# moire_v1_2_rtb.net
KiCad netlist of a schematic drawn in EAGLE
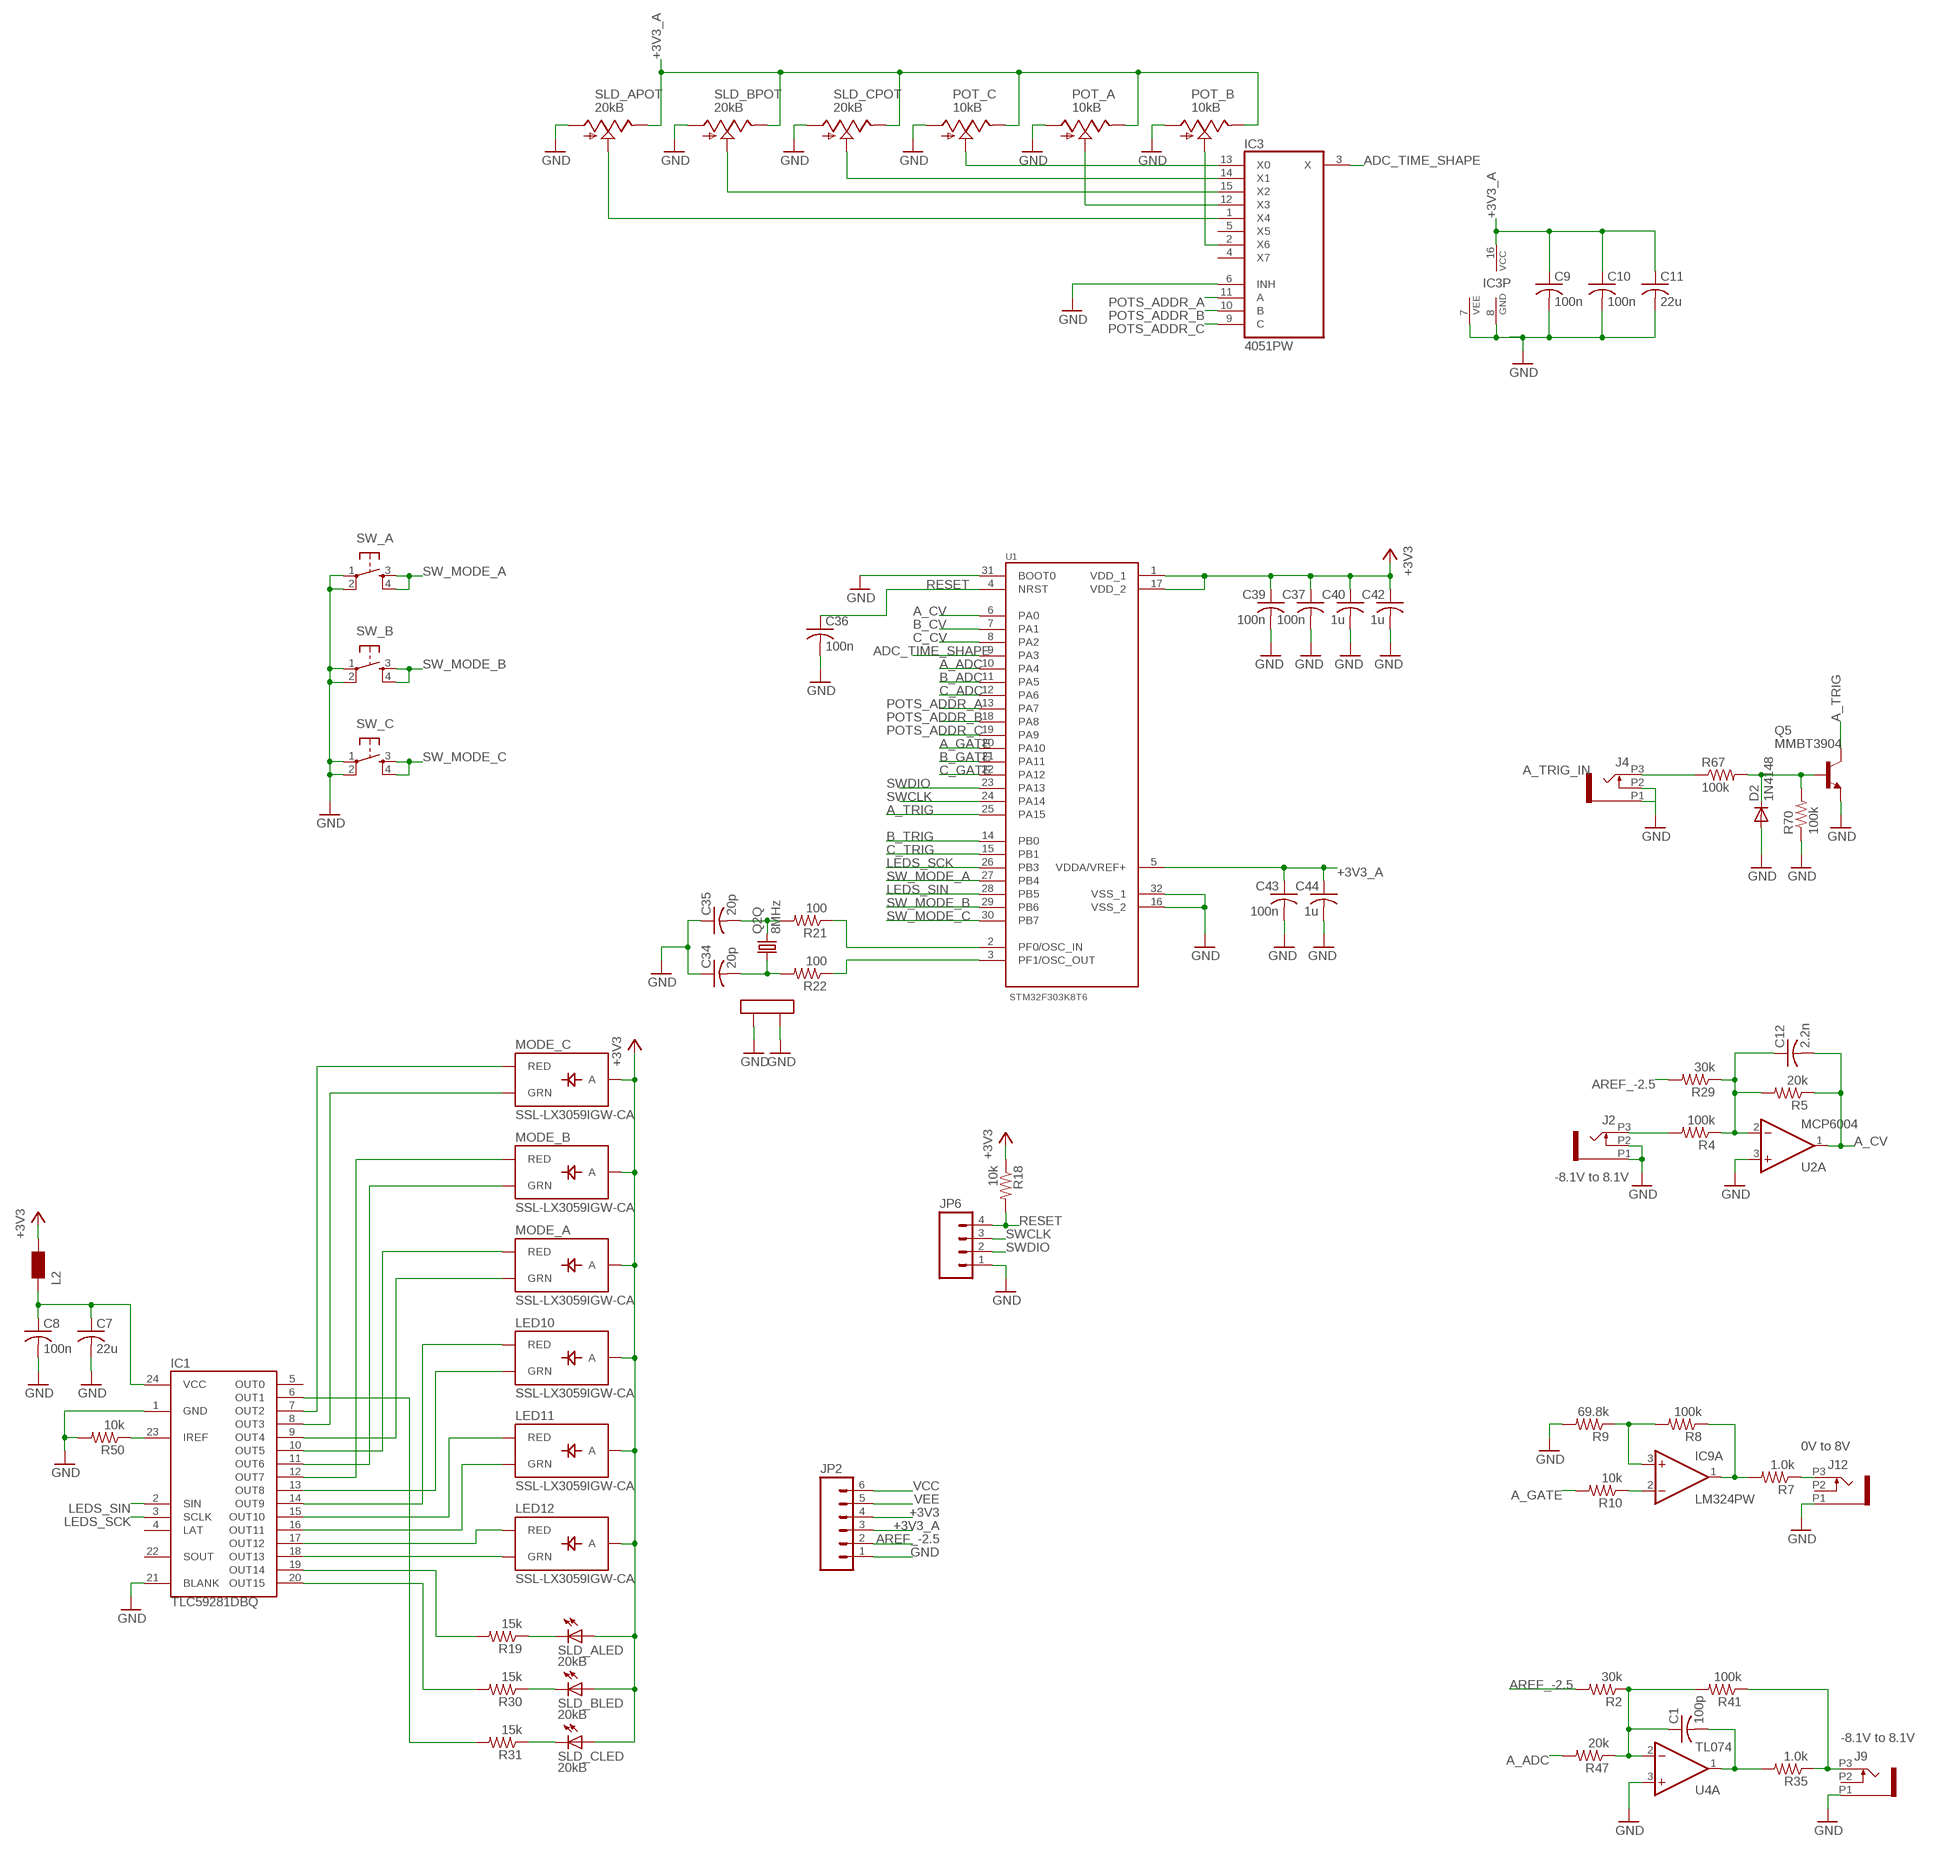
[diagram p0: schematic, sheet 1, part 1 of 2]
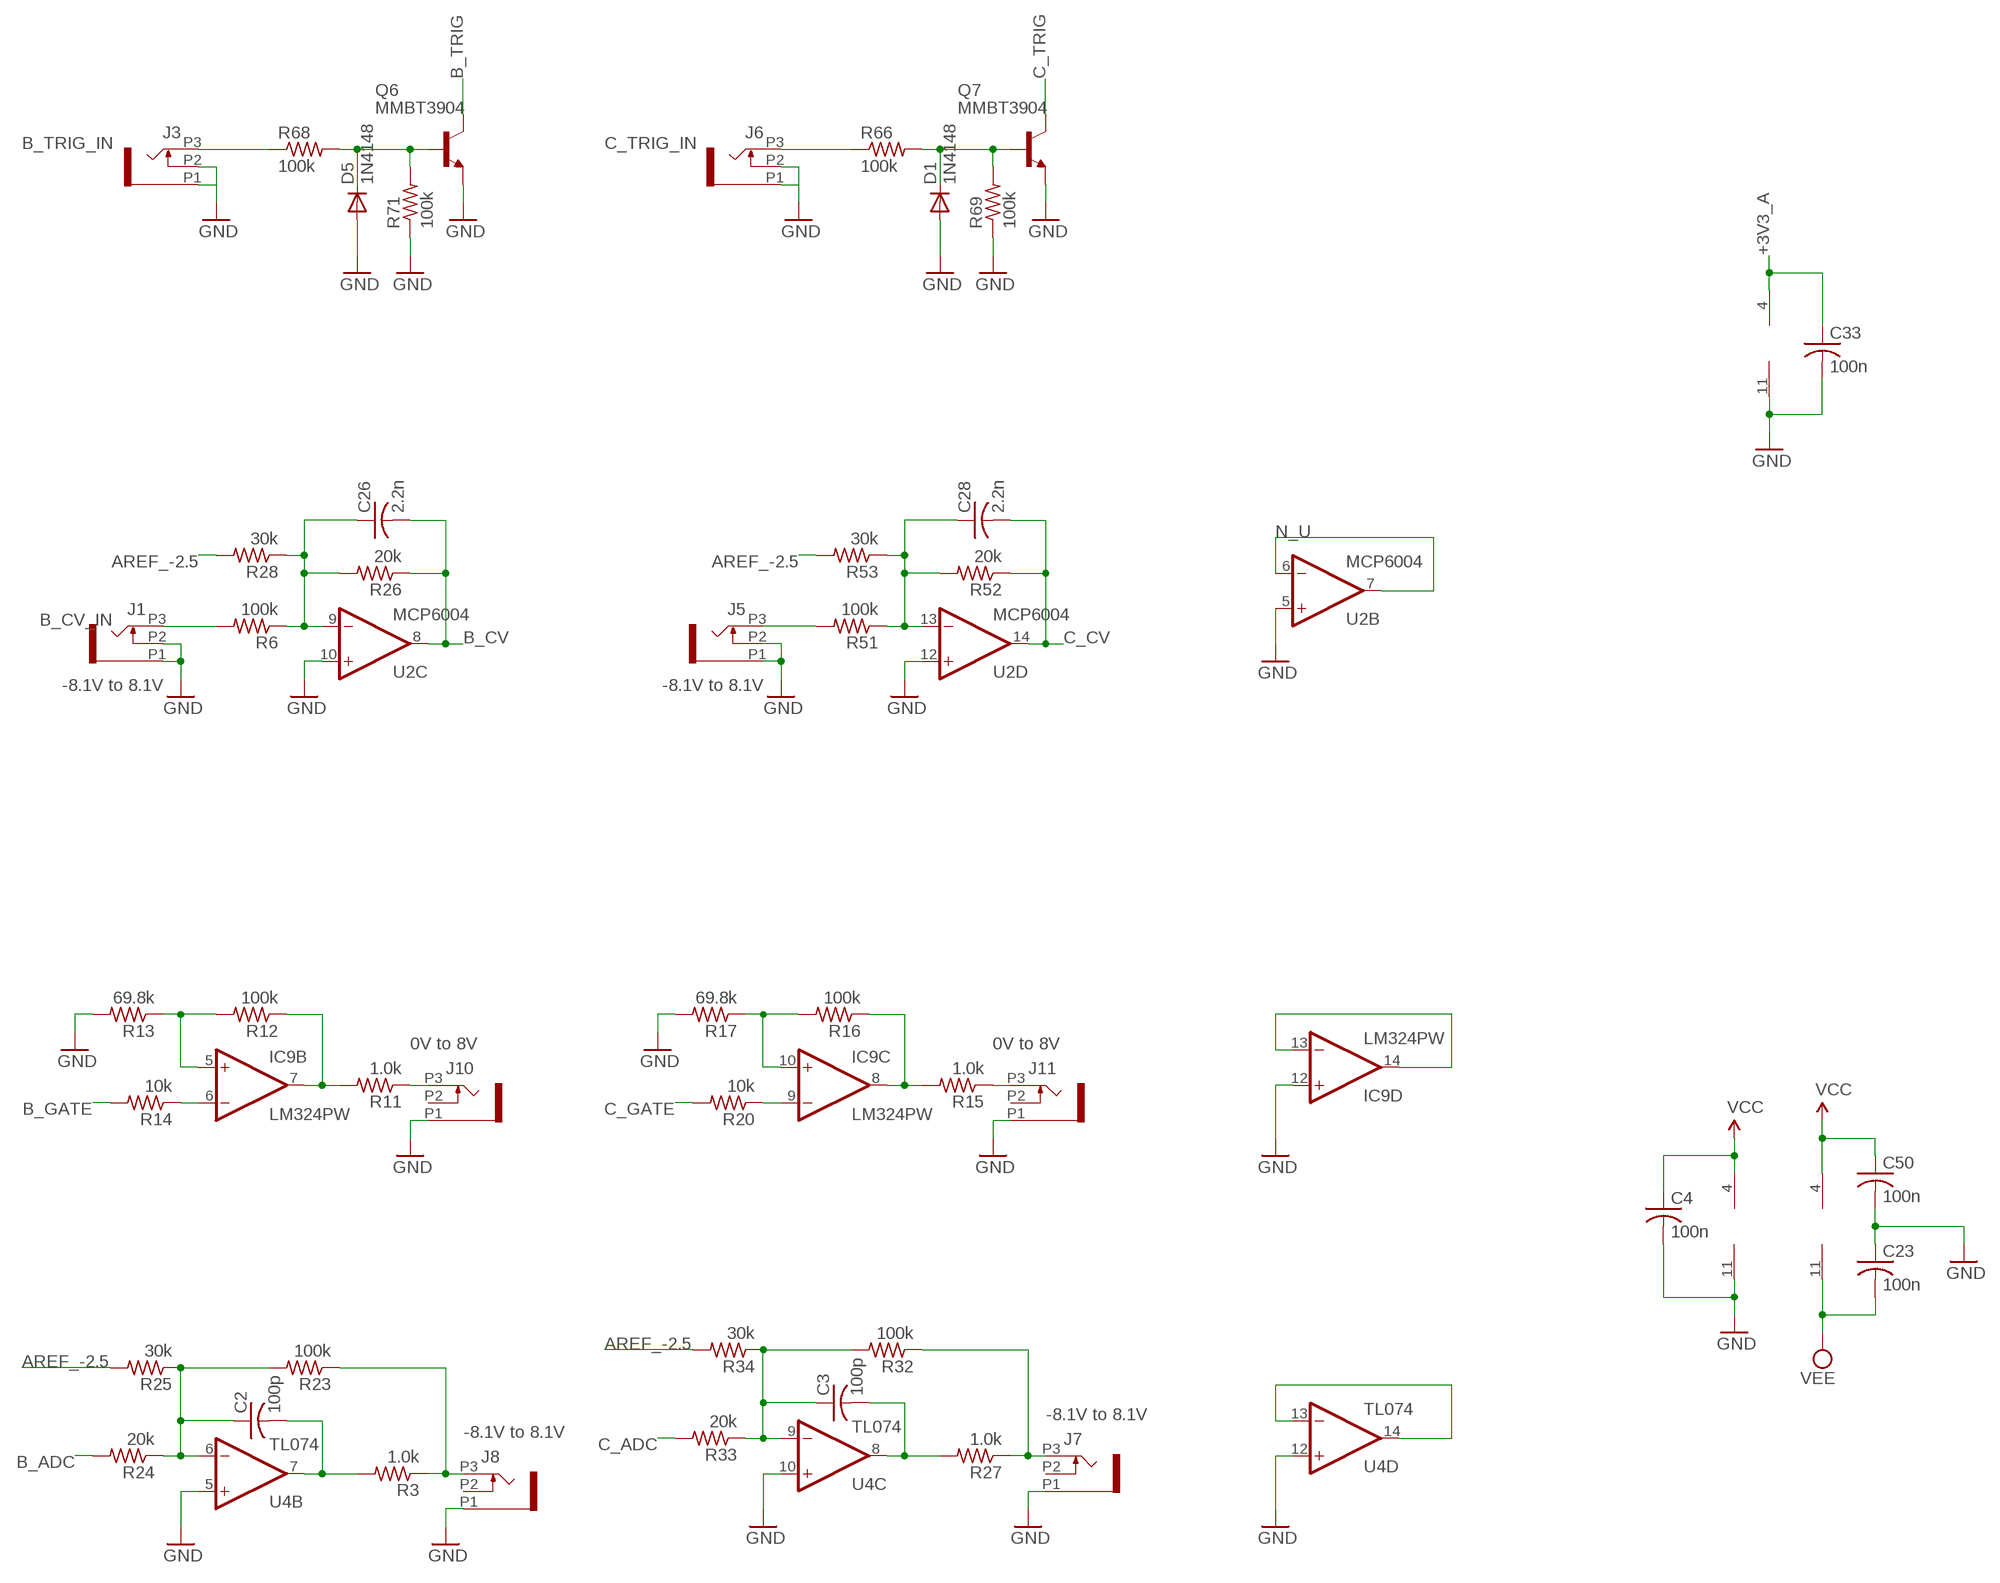
[diagram p1: schematic, sheet 1, part 2 of 2]
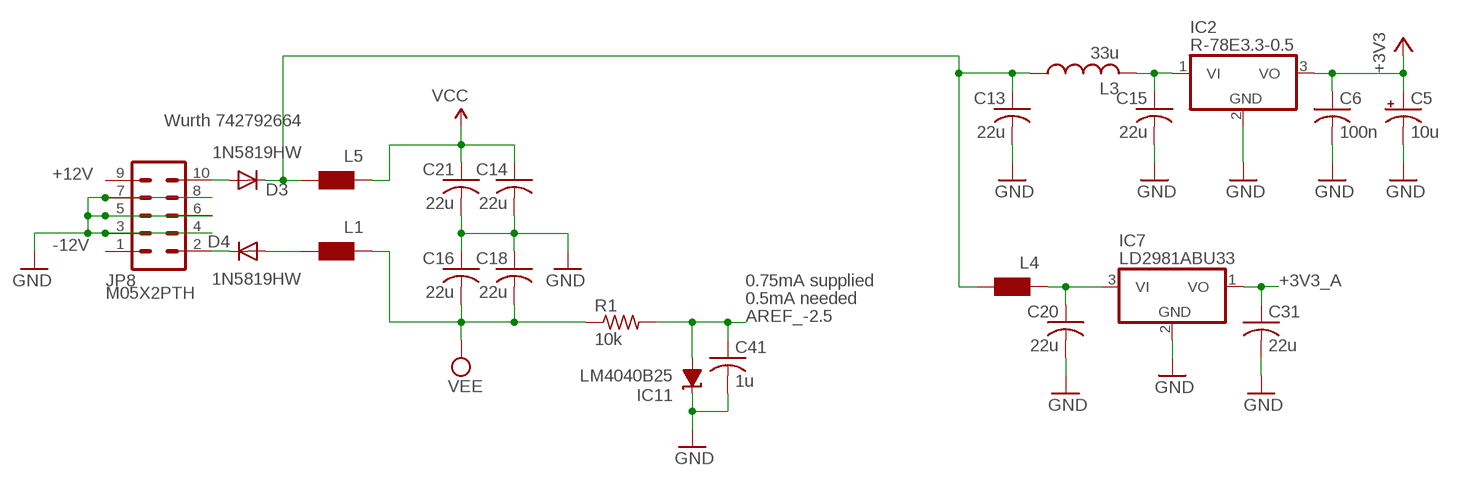
[diagram p2: schematic, sheet 2]

(export (version "E")
  (design (tool "Eeschema 10.0.6"))
  (components
    (comp (ref "C5")
      (value "10u")
      (footprint "eagle-import:PANASONIC_A")
      (libsource (lib "eagle-import") (part "CPOL-USA"))
    )
    (comp (ref "C6")
      (value "100n")
      (footprint "eagle-import:C0603")
      (libsource (lib "eagle-import") (part "C-USC0603"))
    )
    (comp (ref "C13")
      (value "22u")
      (footprint "eagle-import:C1206")
      (libsource (lib "eagle-import") (part "C-USC1206"))
    )
    (comp (ref "C14")
      (value "22u")
      (footprint "eagle-import:C1206")
      (libsource (lib "eagle-import") (part "C-USC1206"))
    )
    (comp (ref "C15")
      (value "22u")
      (footprint "eagle-import:C1206")
      (libsource (lib "eagle-import") (part "C-USC1206"))
    )
    (comp (ref "C16")
      (value "22u")
      (footprint "eagle-import:C1206")
      (libsource (lib "eagle-import") (part "C-USC1206"))
    )
    (comp (ref "C18")
      (value "22u")
      (footprint "eagle-import:C1206")
      (libsource (lib "eagle-import") (part "C-USC1206"))
    )
    (comp (ref "C20")
      (value "22u")
      (footprint "eagle-import:C1206")
      (libsource (lib "eagle-import") (part "C-USC1206"))
    )
    (comp (ref "C21")
      (value "22u")
      (footprint "eagle-import:C1206")
      (libsource (lib "eagle-import") (part "C-USC1206"))
    )
    (comp (ref "C31")
      (value "22u")
      (footprint "eagle-import:C1206")
      (libsource (lib "eagle-import") (part "C-USC1206"))
    )
    (comp (ref "C41")
      (value "1u")
      (footprint "eagle-import:C0603")
      (libsource (lib "eagle-import") (part "C-USC0603"))
    )
    (comp (ref "D3")
      (value "1N5819HW")
      (footprint "eagle-import:SOD123")
      (libsource (lib "eagle-import") (part "DIODE-SOD123"))
    )
    (comp (ref "D4")
      (value "1N5819HW")
      (footprint "eagle-import:SOD123")
      (libsource (lib "eagle-import") (part "DIODE-SOD123"))
    )
    (comp (ref "IC2")
      (value "R-78E3.3-0.5")
      (footprint "eagle-import:WE78")
      (libsource (lib "eagle-import") (part "WE173950378"))
    )
    (comp (ref "IC7")
      (value "LD2981ABU33")
      (footprint "eagle-import:SOT89")
      (libsource (lib "eagle-import") (part "LD2981ABU"))
    )
    (comp (ref "IC11")
      (value "LM4040B25")
      (footprint "eagle-import:DBZ_R-PDSO-G3")
      (libsource (lib "eagle-import") (part "LM4041DBZB12"))
    )
    (comp (ref "JP8")
      (value "M05X2PTH")
      (footprint "eagle-import:2X5-PTH")
      (libsource (lib "eagle-import") (part "M05X2PTH"))
    )
    (comp (ref "L1")
      (value "WE-CBF_0603")
      (footprint "eagle-import:0603")
      (libsource (lib "eagle-import") (part "WE-CBF_0603"))
    )
    (comp (ref "L3")
      (value "33u")
      (footprint "eagle-import:L2012C")
      (libsource (lib "eagle-import") (part "L-USL2012C"))
    )
    (comp (ref "L4")
      (value "WE-CBF_0603")
      (footprint "eagle-import:0603")
      (libsource (lib "eagle-import") (part "WE-CBF_0603"))
    )
    (comp (ref "L5")
      (value "WE-CBF_0603")
      (footprint "eagle-import:0603")
      (libsource (lib "eagle-import") (part "WE-CBF_0603"))
    )
    (comp (ref "R1")
      (value "10k")
      (footprint "eagle-import:R0603")
      (libsource (lib "eagle-import") (part "R-US_R0603"))
    )
    (comp (ref "C1")
      (value "100p")
      (footprint "eagle-import:C0603")
      (libsource (lib "eagle-import") (part "C-USC0603"))
    )
    (comp (ref "C2")
      (value "100p")
      (footprint "eagle-import:C0603")
      (libsource (lib "eagle-import") (part "C-USC0603"))
    )
    (comp (ref "C3")
      (value "100p")
      (footprint "eagle-import:C0603")
      (libsource (lib "eagle-import") (part "C-USC0603"))
    )
    (comp (ref "C4")
      (value "100n")
      (footprint "eagle-import:C0603")
      (libsource (lib "eagle-import") (part "C-USC0603"))
    )
    (comp (ref "C7")
      (value "22u")
      (footprint "eagle-import:C1206")
      (libsource (lib "eagle-import") (part "C-USC1206"))
    )
    (comp (ref "C8")
      (value "100n")
      (footprint "eagle-import:C0603")
      (libsource (lib "eagle-import") (part "C-USC0603"))
    )
    (comp (ref "C9")
      (value "100n")
      (footprint "eagle-import:C0603")
      (libsource (lib "eagle-import") (part "C-USC0603"))
    )
    (comp (ref "C10")
      (value "100n")
      (footprint "eagle-import:C0603")
      (libsource (lib "eagle-import") (part "C-USC0603"))
    )
    (comp (ref "C11")
      (value "22u")
      (footprint "eagle-import:C1206")
      (libsource (lib "eagle-import") (part "C-USC1206"))
    )
    (comp (ref "C12")
      (value "2.2n")
      (footprint "eagle-import:C0603")
      (libsource (lib "eagle-import") (part "C-USC0603"))
    )
    (comp (ref "C23")
      (value "100n")
      (footprint "eagle-import:C0603")
      (libsource (lib "eagle-import") (part "C-USC0603"))
    )
    (comp (ref "C26")
      (value "2.2n")
      (footprint "eagle-import:C0603")
      (libsource (lib "eagle-import") (part "C-USC0603"))
    )
    (comp (ref "C28")
      (value "2.2n")
      (footprint "eagle-import:C0603")
      (libsource (lib "eagle-import") (part "C-USC0603"))
    )
    (comp (ref "C33")
      (value "100n")
      (footprint "eagle-import:C0603")
      (libsource (lib "eagle-import") (part "C-USC0603"))
    )
    (comp (ref "C34")
      (value "20p")
      (footprint "eagle-import:C0603")
      (libsource (lib "eagle-import") (part "C-USC0603"))
    )
    (comp (ref "C35")
      (value "20p")
      (footprint "eagle-import:C0603")
      (libsource (lib "eagle-import") (part "C-USC0603"))
    )
    (comp (ref "C36")
      (value "100n")
      (footprint "eagle-import:C0603")
      (libsource (lib "eagle-import") (part "C-USC0603"))
    )
    (comp (ref "C37")
      (value "100n")
      (footprint "eagle-import:C0603")
      (libsource (lib "eagle-import") (part "C-USC0603"))
    )
    (comp (ref "C39")
      (value "100n")
      (footprint "eagle-import:C0603")
      (libsource (lib "eagle-import") (part "C-USC0603"))
    )
    (comp (ref "C40")
      (value "1u")
      (footprint "eagle-import:C0603")
      (libsource (lib "eagle-import") (part "C-USC0603"))
    )
    (comp (ref "C42")
      (value "1u")
      (footprint "eagle-import:C0603")
      (libsource (lib "eagle-import") (part "C-USC0603"))
    )
    (comp (ref "C43")
      (value "100n")
      (footprint "eagle-import:C0603")
      (libsource (lib "eagle-import") (part "C-USC0603"))
    )
    (comp (ref "C44")
      (value "1u")
      (footprint "eagle-import:C0603")
      (libsource (lib "eagle-import") (part "C-USC0603"))
    )
    (comp (ref "C50")
      (value "100n")
      (footprint "eagle-import:C0603")
      (libsource (lib "eagle-import") (part "C-USC0603"))
    )
    (comp (ref "D1")
      (value "1N4148")
      (footprint "eagle-import:SOD523")
      (libsource (lib "eagle-import") (part "DIODE-SOD523"))
    )
    (comp (ref "D2")
      (value "1N4148")
      (footprint "eagle-import:SOD523")
      (libsource (lib "eagle-import") (part "DIODE-SOD523"))
    )
    (comp (ref "D5")
      (value "1N4148")
      (footprint "eagle-import:SOD523")
      (libsource (lib "eagle-import") (part "DIODE-SOD523"))
    )
    (comp (ref "IC1")
      (value "TLC59281DBQ")
      (footprint "eagle-import:TSSOP24_0635")
      (libsource (lib "eagle-import") (part "TLC59281DBQ"))
    )
    (comp (ref "IC3")
      (value "4051PW")
      (footprint "eagle-import:TSSOP16_065")
      (libsource (lib "eagle-import") (part "4051PW"))
    )
    (comp (ref "IC9")
      (value "LM324PW")
      (footprint "eagle-import:TSSOP14_065")
      (libsource (lib "eagle-import") (part "TL074PW"))
    )
    (comp (ref "J1")
      (value "PJ301_THONKICONN6")
      (footprint "eagle-import:WQP_PJ_301M6")
      (libsource (lib "eagle-import") (part "PJ301_THONKICONN6"))
    )
    (comp (ref "J2")
      (value "PJ301_THONKICONN6")
      (footprint "eagle-import:WQP_PJ_301M6")
      (libsource (lib "eagle-import") (part "PJ301_THONKICONN6"))
    )
    (comp (ref "J3")
      (value "PJ301_THONKICONN6")
      (footprint "eagle-import:WQP_PJ_301M6")
      (libsource (lib "eagle-import") (part "PJ301_THONKICONN6"))
    )
    (comp (ref "J4")
      (value "PJ301_THONKICONN6")
      (footprint "eagle-import:WQP_PJ_301M6")
      (libsource (lib "eagle-import") (part "PJ301_THONKICONN6"))
    )
    (comp (ref "J5")
      (value "PJ301_THONKICONN6")
      (footprint "eagle-import:WQP_PJ_301M6")
      (libsource (lib "eagle-import") (part "PJ301_THONKICONN6"))
    )
    (comp (ref "J6")
      (value "PJ301_THONKICONN6")
      (footprint "eagle-import:WQP_PJ_301M6")
      (libsource (lib "eagle-import") (part "PJ301_THONKICONN6"))
    )
    (comp (ref "J7")
      (value "PJ301_THONKICONN6")
      (footprint "eagle-import:WQP_PJ_301M6")
      (libsource (lib "eagle-import") (part "PJ301_THONKICONN6"))
    )
    (comp (ref "J8")
      (value "PJ301_THONKICONN6")
      (footprint "eagle-import:WQP_PJ_301M6")
      (libsource (lib "eagle-import") (part "PJ301_THONKICONN6"))
    )
    (comp (ref "J9")
      (value "PJ301_THONKICONN6")
      (footprint "eagle-import:WQP_PJ_301M6")
      (libsource (lib "eagle-import") (part "PJ301_THONKICONN6"))
    )
    (comp (ref "J10")
      (value "PJ301_THONKICONN6")
      (footprint "eagle-import:WQP_PJ_301M6")
      (libsource (lib "eagle-import") (part "PJ301_THONKICONN6"))
    )
    (comp (ref "J11")
      (value "PJ301_THONKICONN6")
      (footprint "eagle-import:WQP_PJ_301M6")
      (libsource (lib "eagle-import") (part "PJ301_THONKICONN6"))
    )
    (comp (ref "J12")
      (value "PJ301_THONKICONN6")
      (footprint "eagle-import:WQP_PJ_301M6")
      (libsource (lib "eagle-import") (part "PJ301_THONKICONN6"))
    )
    (comp (ref "JP2")
      (value "M06SIP")
      (footprint "eagle-import:1X06")
      (libsource (lib "eagle-import") (part "M06SIP"))
    )
    (comp (ref "JP6")
      (value "M04PTH")
      (footprint "eagle-import:1X04")
      (libsource (lib "eagle-import") (part "M04PTH"))
    )
    (comp (ref "L2")
      (value "WE-CBF_0603")
      (footprint "eagle-import:0603")
      (libsource (lib "eagle-import") (part "WE-CBF_0603"))
    )
    (comp (ref "LED10")
      (value "SSL-LX3059IGW-CA")
      (footprint "eagle-import:LED-BICOLOR-THROUGHHOLE-LUMEX")
      (libsource (lib "eagle-import") (part "LED-BICOLOR-THROUGHHOLE-CA"))
    )
    (comp (ref "LED11")
      (value "SSL-LX3059IGW-CA")
      (footprint "eagle-import:LED-BICOLOR-THROUGHHOLE-LUMEX")
      (libsource (lib "eagle-import") (part "LED-BICOLOR-THROUGHHOLE-CA"))
    )
    (comp (ref "LED12")
      (value "SSL-LX3059IGW-CA")
      (footprint "eagle-import:LED-BICOLOR-THROUGHHOLE-LUMEX")
      (libsource (lib "eagle-import") (part "LED-BICOLOR-THROUGHHOLE-CA"))
    )
    (comp (ref "MODE_A")
      (value "SSL-LX3059IGW-CA")
      (footprint "eagle-import:LED-BICOLOR-THROUGHHOLE-LUMEX")
      (libsource (lib "eagle-import") (part "LED-BICOLOR-THROUGHHOLE-CA"))
    )
    (comp (ref "MODE_B")
      (value "SSL-LX3059IGW-CA")
      (footprint "eagle-import:LED-BICOLOR-THROUGHHOLE-LUMEX")
      (libsource (lib "eagle-import") (part "LED-BICOLOR-THROUGHHOLE-CA"))
    )
    (comp (ref "MODE_C")
      (value "SSL-LX3059IGW-CA")
      (footprint "eagle-import:LED-BICOLOR-THROUGHHOLE-LUMEX")
      (libsource (lib "eagle-import") (part "LED-BICOLOR-THROUGHHOLE-CA"))
    )
    (comp (ref "POT_A")
      (value "10kB")
      (footprint "eagle-import:ALPS_POT_VERTICAL")
      (libsource (lib "eagle-import") (part "POT_USVERTICAL"))
    )
    (comp (ref "POT_B")
      (value "10kB")
      (footprint "eagle-import:ALPS_POT_VERTICAL")
      (libsource (lib "eagle-import") (part "POT_USVERTICAL"))
    )
    (comp (ref "POT_C")
      (value "10kB")
      (footprint "eagle-import:ALPS_POT_VERTICAL")
      (libsource (lib "eagle-import") (part "POT_USVERTICAL"))
    )
    (comp (ref "Q2")
      (value "8MHz")
      (footprint "eagle-import:CTS406")
      (libsource (lib "eagle-import") (part "CRYSTAL"))
    )
    (comp (ref "Q5")
      (value "MMBT3904")
      (footprint "eagle-import:SOT23-BEC")
      (libsource (lib "eagle-import") (part "-NPN-SOT23-BECMMBT3904LT1"))
    )
    (comp (ref "Q6")
      (value "MMBT3904")
      (footprint "eagle-import:SOT23-BEC")
      (libsource (lib "eagle-import") (part "-NPN-SOT23-BECMMBT3904LT1"))
    )
    (comp (ref "Q7")
      (value "MMBT3904")
      (footprint "eagle-import:SOT23-BEC")
      (libsource (lib "eagle-import") (part "-NPN-SOT23-BECMMBT3904LT1"))
    )
    (comp (ref "R2")
      (value "30k")
      (footprint "eagle-import:R0603")
      (libsource (lib "eagle-import") (part "R-US_R0603"))
    )
    (comp (ref "R3")
      (value "1.0k")
      (footprint "eagle-import:R0603")
      (libsource (lib "eagle-import") (part "R-US_R0603"))
    )
    (comp (ref "R4")
      (value "100k")
      (footprint "eagle-import:R0603")
      (libsource (lib "eagle-import") (part "R-US_R0603"))
    )
    (comp (ref "R5")
      (value "20k")
      (footprint "eagle-import:R0603")
      (libsource (lib "eagle-import") (part "R-US_R0603"))
    )
    (comp (ref "R6")
      (value "100k")
      (footprint "eagle-import:R0603")
      (libsource (lib "eagle-import") (part "R-US_R0603"))
    )
    (comp (ref "R7")
      (value "1.0k")
      (footprint "eagle-import:R0603")
      (libsource (lib "eagle-import") (part "R-US_R0603"))
    )
    (comp (ref "R8")
      (value "100k")
      (footprint "eagle-import:R0603")
      (libsource (lib "eagle-import") (part "R-US_R0603"))
    )
    (comp (ref "R9")
      (value "69.8k")
      (footprint "eagle-import:R0603")
      (libsource (lib "eagle-import") (part "R-US_R0603"))
    )
    (comp (ref "R10")
      (value "10k")
      (footprint "eagle-import:R0603")
      (libsource (lib "eagle-import") (part "R-US_R0603"))
    )
    (comp (ref "R11")
      (value "1.0k")
      (footprint "eagle-import:R0603")
      (libsource (lib "eagle-import") (part "R-US_R0603"))
    )
    (comp (ref "R12")
      (value "100k")
      (footprint "eagle-import:R0603")
      (libsource (lib "eagle-import") (part "R-US_R0603"))
    )
    (comp (ref "R13")
      (value "69.8k")
      (footprint "eagle-import:R0603")
      (libsource (lib "eagle-import") (part "R-US_R0603"))
    )
    (comp (ref "R14")
      (value "10k")
      (footprint "eagle-import:R0603")
      (libsource (lib "eagle-import") (part "R-US_R0603"))
    )
    (comp (ref "R15")
      (value "1.0k")
      (footprint "eagle-import:R0603")
      (libsource (lib "eagle-import") (part "R-US_R0603"))
    )
    (comp (ref "R16")
      (value "100k")
      (footprint "eagle-import:R0603")
      (libsource (lib "eagle-import") (part "R-US_R0603"))
    )
    (comp (ref "R17")
      (value "69.8k")
      (footprint "eagle-import:R0603")
      (libsource (lib "eagle-import") (part "R-US_R0603"))
    )
    (comp (ref "R18")
      (value "10k")
      (footprint "eagle-import:R0603")
      (libsource (lib "eagle-import") (part "R-US_R0603"))
    )
    (comp (ref "R19")
      (value "15k")
      (footprint "eagle-import:R0603")
      (libsource (lib "eagle-import") (part "R-US_R0603"))
    )
    (comp (ref "R20")
      (value "10k")
      (footprint "eagle-import:R0603")
      (libsource (lib "eagle-import") (part "R-US_R0603"))
    )
    (comp (ref "R21")
      (value "100")
      (footprint "eagle-import:R0603")
      (libsource (lib "eagle-import") (part "R-US_R0603"))
    )
    (comp (ref "R22")
      (value "100")
      (footprint "eagle-import:R0603")
      (libsource (lib "eagle-import") (part "R-US_R0603"))
    )
    (comp (ref "R23")
      (value "100k")
      (footprint "eagle-import:R0603")
      (libsource (lib "eagle-import") (part "R-US_R0603"))
    )
    (comp (ref "R24")
      (value "20k")
      (footprint "eagle-import:R0603")
      (libsource (lib "eagle-import") (part "R-US_R0603"))
    )
    (comp (ref "R25")
      (value "30k")
      (footprint "eagle-import:R0603")
      (libsource (lib "eagle-import") (part "R-US_R0603"))
    )
    (comp (ref "R26")
      (value "20k")
      (footprint "eagle-import:R0603")
      (libsource (lib "eagle-import") (part "R-US_R0603"))
    )
    (comp (ref "R27")
      (value "1.0k")
      (footprint "eagle-import:R0603")
      (libsource (lib "eagle-import") (part "R-US_R0603"))
    )
    (comp (ref "R28")
      (value "30k")
      (footprint "eagle-import:R0603")
      (libsource (lib "eagle-import") (part "R-US_R0603"))
    )
    (comp (ref "R29")
      (value "30k")
      (footprint "eagle-import:R0603")
      (libsource (lib "eagle-import") (part "R-US_R0603"))
    )
    (comp (ref "R30")
      (value "15k")
      (footprint "eagle-import:R0603")
      (libsource (lib "eagle-import") (part "R-US_R0603"))
    )
    (comp (ref "R31")
      (value "15k")
      (footprint "eagle-import:R0603")
      (libsource (lib "eagle-import") (part "R-US_R0603"))
    )
    (comp (ref "R32")
      (value "100k")
      (footprint "eagle-import:R0603")
      (libsource (lib "eagle-import") (part "R-US_R0603"))
    )
    (comp (ref "R33")
      (value "20k")
      (footprint "eagle-import:R0603")
      (libsource (lib "eagle-import") (part "R-US_R0603"))
    )
    (comp (ref "R34")
      (value "30k")
      (footprint "eagle-import:R0603")
      (libsource (lib "eagle-import") (part "R-US_R0603"))
    )
    (comp (ref "R35")
      (value "1.0k")
      (footprint "eagle-import:R0603")
      (libsource (lib "eagle-import") (part "R-US_R0603"))
    )
    (comp (ref "R41")
      (value "100k")
      (footprint "eagle-import:R0603")
      (libsource (lib "eagle-import") (part "R-US_R0603"))
    )
    (comp (ref "R47")
      (value "20k")
      (footprint "eagle-import:R0603")
      (libsource (lib "eagle-import") (part "R-US_R0603"))
    )
    (comp (ref "R50")
      (value "10k")
      (footprint "eagle-import:R0603")
      (libsource (lib "eagle-import") (part "R-US_R0603"))
    )
    (comp (ref "R51")
      (value "100k")
      (footprint "eagle-import:R0603")
      (libsource (lib "eagle-import") (part "R-US_R0603"))
    )
    (comp (ref "R52")
      (value "20k")
      (footprint "eagle-import:R0603")
      (libsource (lib "eagle-import") (part "R-US_R0603"))
    )
    (comp (ref "R53")
      (value "30k")
      (footprint "eagle-import:R0603")
      (libsource (lib "eagle-import") (part "R-US_R0603"))
    )
    (comp (ref "R66")
      (value "100k")
      (footprint "eagle-import:R0603")
      (libsource (lib "eagle-import") (part "R-US_R0603"))
    )
    (comp (ref "R67")
      (value "100k")
      (footprint "eagle-import:R0603")
      (libsource (lib "eagle-import") (part "R-US_R0603"))
    )
    (comp (ref "R68")
      (value "100k")
      (footprint "eagle-import:R0603")
      (libsource (lib "eagle-import") (part "R-US_R0603"))
    )
    (comp (ref "R69")
      (value "100k")
      (footprint "eagle-import:R0603")
      (libsource (lib "eagle-import") (part "R-US_R0603"))
    )
    (comp (ref "R70")
      (value "100k")
      (footprint "eagle-import:R0603")
      (libsource (lib "eagle-import") (part "R-US_R0603"))
    )
    (comp (ref "R71")
      (value "100k")
      (footprint "eagle-import:R0603")
      (libsource (lib "eagle-import") (part "R-US_R0603"))
    )
    (comp (ref "SLD_A")
      (value "20kB")
      (footprint "eagle-import:BOURNS_SLIDER")
      (libsource (lib "eagle-import") (part "BOURNS_SLIDER"))
    )
    (comp (ref "SLD_B")
      (value "20kB")
      (footprint "eagle-import:BOURNS_SLIDER")
      (libsource (lib "eagle-import") (part "BOURNS_SLIDER"))
    )
    (comp (ref "SLD_C")
      (value "20kB")
      (footprint "eagle-import:BOURNS_SLIDER")
      (libsource (lib "eagle-import") (part "BOURNS_SLIDER"))
    )
    (comp (ref "SW_A")
      (value "TAC_SWITCHPTH")
      (footprint "eagle-import:TACTILE-PTH")
      (libsource (lib "eagle-import") (part "TAC_SWITCHPTH"))
    )
    (comp (ref "SW_B")
      (value "TAC_SWITCHPTH")
      (footprint "eagle-import:TACTILE-PTH")
      (libsource (lib "eagle-import") (part "TAC_SWITCHPTH"))
    )
    (comp (ref "SW_C")
      (value "TAC_SWITCHPTH")
      (footprint "eagle-import:TACTILE-PTH")
      (libsource (lib "eagle-import") (part "TAC_SWITCHPTH"))
    )
    (comp (ref "U1")
      (value "STM32F303K8T6")
      (footprint "eagle-import:QFP80P900X900X160-32N")
      (fields (field (name "MF") "STMicroelectronics"))
      (libsource (lib "eagle-import") (part "STM32F303K8T6"))
    )
    (comp (ref "U2")
      (value "MCP6004")
      (footprint "eagle-import:SO14")
      (libsource (lib "eagle-import") (part "MCP6004_SMD"))
    )
    (comp (ref "U4")
      (value "TL074")
      (footprint "eagle-import:SO14")
      (libsource (lib "eagle-import") (part "TL074_SMD"))
    )
  )
  (nets
    (net (code "1") (name "+3V3") (class "Default")
      (node (ref "C37") (pin "1") (pinfunction "1_1") (pintype "passive"))
      (node (ref "C39") (pin "1") (pinfunction "1_1") (pintype "passive"))
      (node (ref "C40") (pin "1") (pinfunction "1_1") (pintype "passive"))
      (node (ref "C42") (pin "1") (pinfunction "1_1") (pintype "passive"))
      (node (ref "C5") (pin "+") (pinfunction "+_+") (pintype "passive"))
      (node (ref "C6") (pin "1") (pinfunction "1_1") (pintype "passive"))
      (node (ref "IC2") (pin "3") (pinfunction "VO_3") (pintype "passive"))
      (node (ref "JP2") (pin "4") (pinfunction "4_4") (pintype "passive"))
      (node (ref "L2") (pin "2") (pinfunction "2_2") (pintype "passive"))
      (node (ref "LED10") (pin "A") (pinfunction "A_A") (pintype "bidirectional"))
      (node (ref "LED11") (pin "A") (pinfunction "A_A") (pintype "bidirectional"))
      (node (ref "LED12") (pin "A") (pinfunction "A_A") (pintype "bidirectional"))
      (node (ref "MODE_A") (pin "A") (pinfunction "A_A") (pintype "bidirectional"))
      (node (ref "MODE_B") (pin "A") (pinfunction "A_A") (pintype "bidirectional"))
      (node (ref "MODE_C") (pin "A") (pinfunction "A_A") (pintype "bidirectional"))
      (node (ref "R18") (pin "1") (pinfunction "1_1") (pintype "passive"))
      (node (ref "SLD_A") (pin "B") (pinfunction "A_B") (pintype "passive"))
      (node (ref "SLD_B") (pin "B") (pinfunction "A_B") (pintype "passive"))
      (node (ref "SLD_C") (pin "B") (pinfunction "A_B") (pintype "passive"))
      (node (ref "U1") (pin "1") (pinfunction "VDD_1_1") (pintype "power_in"))
      (node (ref "U1") (pin "17") (pinfunction "VDD_2_17") (pintype "power_in"))
    )
    (net (code "2") (name "+3V3_A") (class "Default")
      (node (ref "C10") (pin "1") (pinfunction "1_1") (pintype "passive"))
      (node (ref "C11") (pin "1") (pinfunction "1_1") (pintype "passive"))
      (node (ref "C31") (pin "1") (pinfunction "1_1") (pintype "passive"))
      (node (ref "C33") (pin "1") (pinfunction "1_1") (pintype "passive"))
      (node (ref "C43") (pin "1") (pinfunction "1_1") (pintype "passive"))
      (node (ref "C44") (pin "1") (pinfunction "1_1") (pintype "passive"))
      (node (ref "C9") (pin "1") (pinfunction "1_1") (pintype "passive"))
      (node (ref "IC3") (pin "16") (pinfunction "VCC_16") (pintype "power_in"))
      (node (ref "IC7") (pin "1") (pinfunction "VO_1") (pintype "passive"))
      (node (ref "JP2") (pin "3") (pinfunction "3_3") (pintype "passive"))
      (node (ref "POT_A") (pin "P$1") (pinfunction "E_P$1") (pintype "passive"))
      (node (ref "POT_B") (pin "P$1") (pinfunction "E_P$1") (pintype "passive"))
      (node (ref "POT_C") (pin "P$1") (pinfunction "E_P$1") (pintype "passive"))
      (node (ref "SLD_A") (pin "3") (pinfunction "E_3") (pintype "passive"))
      (node (ref "SLD_B") (pin "3") (pinfunction "E_3") (pintype "passive"))
      (node (ref "SLD_C") (pin "3") (pinfunction "E_3") (pintype "passive"))
      (node (ref "U1") (pin "5") (pinfunction "VDDA/VREF+_5") (pintype "power_in"))
      (node (ref "U2") (pin "4") (pinfunction "V+_4") (pintype "power_in"))
    )
    (net (code "3") (name "+12V") (class "Default")
      (node (ref "D3") (pin "A") (pinfunction "A_A") (pintype "passive"))
      (node (ref "JP8") (pin "10") (pinfunction "10_10") (pintype "passive"))
      (node (ref "JP8") (pin "9") (pinfunction "9_9") (pintype "passive"))
    )
    (net (code "4") (name "-12V") (class "Default")
      (node (ref "D4") (pin "C") (pinfunction "C_C") (pintype "passive"))
      (node (ref "JP8") (pin "1") (pinfunction "1_1") (pintype "passive"))
      (node (ref "JP8") (pin "2") (pinfunction "2_2") (pintype "passive"))
    )
    (net (code "5") (name "ADC_TIME_SHAPE") (class "Default")
      (node (ref "IC3") (pin "3") (pinfunction "X_3") (pintype "bidirectional"))
      (node (ref "U1") (pin "9") (pinfunction "PA3_9") (pintype "bidirectional"))
    )
    (net (code "6") (name "AREF_-2.5") (class "Default")
      (node (ref "C41") (pin "1") (pinfunction "1_1") (pintype "passive"))
      (node (ref "IC11") (pin "2") (pinfunction "A_2") (pintype "passive"))
      (node (ref "JP2") (pin "2") (pinfunction "2_2") (pintype "passive"))
      (node (ref "R1") (pin "2") (pinfunction "2_2") (pintype "passive"))
      (node (ref "R2") (pin "2") (pinfunction "2_2") (pintype "passive"))
      (node (ref "R25") (pin "2") (pinfunction "2_2") (pintype "passive"))
      (node (ref "R28") (pin "2") (pinfunction "2_2") (pintype "passive"))
      (node (ref "R29") (pin "2") (pinfunction "2_2") (pintype "passive"))
      (node (ref "R34") (pin "2") (pinfunction "2_2") (pintype "passive"))
      (node (ref "R53") (pin "2") (pinfunction "2_2") (pintype "passive"))
    )
    (net (code "7") (name "A_ADC") (class "Default")
      (node (ref "R47") (pin "2") (pinfunction "2_2") (pintype "passive"))
      (node (ref "U1") (pin "10") (pinfunction "PA4_10") (pintype "bidirectional"))
    )
    (net (code "8") (name "A_CV") (class "Default")
      (node (ref "C12") (pin "2") (pinfunction "2_2") (pintype "passive"))
      (node (ref "R5") (pin "1") (pinfunction "1_1") (pintype "passive"))
      (node (ref "U1") (pin "6") (pinfunction "PA0_6") (pintype "bidirectional"))
      (node (ref "U2") (pin "1") (pinfunction "OUT_1") (pintype "output"))
    )
    (net (code "9") (name "A_GATE") (class "Default")
      (node (ref "R10") (pin "2") (pinfunction "2_2") (pintype "passive"))
      (node (ref "U1") (pin "20") (pinfunction "PA10_20") (pintype "bidirectional"))
    )
    (net (code "10") (name "A_TRIG") (class "Default")
      (node (ref "Q5") (pin "C") (pinfunction "C_C") (pintype "passive"))
      (node (ref "U1") (pin "25") (pinfunction "PA15_25") (pintype "bidirectional"))
    )
    (net (code "11") (name "A_TRIG_IN") (class "Default")
      (node (ref "J4") (pin "P3") (pinfunction "3_P3") (pintype "passive"))
      (node (ref "R67") (pin "1") (pinfunction "1_1") (pintype "passive"))
    )
    (net (code "12") (name "B_ADC") (class "Default")
      (node (ref "R24") (pin "2") (pinfunction "2_2") (pintype "passive"))
      (node (ref "U1") (pin "11") (pinfunction "PA5_11") (pintype "bidirectional"))
    )
    (net (code "13") (name "B_CV") (class "Default")
      (node (ref "C26") (pin "2") (pinfunction "2_2") (pintype "passive"))
      (node (ref "R26") (pin "1") (pinfunction "1_1") (pintype "passive"))
      (node (ref "U1") (pin "7") (pinfunction "PA1_7") (pintype "bidirectional"))
      (node (ref "U2") (pin "8") (pinfunction "OUT_8") (pintype "output"))
    )
    (net (code "14") (name "B_CV_IN") (class "Default")
      (node (ref "J1") (pin "P3") (pinfunction "3_P3") (pintype "passive"))
      (node (ref "R6") (pin "2") (pinfunction "2_2") (pintype "passive"))
    )
    (net (code "15") (name "B_GATE") (class "Default")
      (node (ref "R14") (pin "2") (pinfunction "2_2") (pintype "passive"))
      (node (ref "U1") (pin "21") (pinfunction "PA11_21") (pintype "bidirectional"))
    )
    (net (code "16") (name "B_TRIG") (class "Default")
      (node (ref "Q6") (pin "C") (pinfunction "C_C") (pintype "passive"))
      (node (ref "U1") (pin "14") (pinfunction "PB0_14") (pintype "bidirectional"))
    )
    (net (code "17") (name "B_TRIG_IN") (class "Default")
      (node (ref "J3") (pin "P3") (pinfunction "3_P3") (pintype "passive"))
      (node (ref "R68") (pin "1") (pinfunction "1_1") (pintype "passive"))
    )
    (net (code "18") (name "C_ADC") (class "Default")
      (node (ref "R33") (pin "2") (pinfunction "2_2") (pintype "passive"))
      (node (ref "U1") (pin "12") (pinfunction "PA6_12") (pintype "bidirectional"))
    )
    (net (code "19") (name "C_CV") (class "Default")
      (node (ref "C28") (pin "2") (pinfunction "2_2") (pintype "passive"))
      (node (ref "R52") (pin "1") (pinfunction "1_1") (pintype "passive"))
      (node (ref "U1") (pin "8") (pinfunction "PA2_8") (pintype "bidirectional"))
      (node (ref "U2") (pin "14") (pinfunction "OUT_14") (pintype "output"))
    )
    (net (code "20") (name "C_GATE") (class "Default")
      (node (ref "R20") (pin "2") (pinfunction "2_2") (pintype "passive"))
      (node (ref "U1") (pin "22") (pinfunction "PA12_22") (pintype "bidirectional"))
    )
    (net (code "21") (name "C_TRIG") (class "Default")
      (node (ref "Q7") (pin "C") (pinfunction "C_C") (pintype "passive"))
      (node (ref "U1") (pin "15") (pinfunction "PB1_15") (pintype "bidirectional"))
    )
    (net (code "22") (name "C_TRIG_IN") (class "Default")
      (node (ref "J6") (pin "P3") (pinfunction "3_P3") (pintype "passive"))
      (node (ref "R66") (pin "1") (pinfunction "1_1") (pintype "passive"))
    )
    (net (code "23") (name "GND") (class "Default")
      (node (ref "C10") (pin "2") (pinfunction "2_2") (pintype "passive"))
      (node (ref "C11") (pin "2") (pinfunction "2_2") (pintype "passive"))
      (node (ref "C13") (pin "2") (pinfunction "2_2") (pintype "passive"))
      (node (ref "C14") (pin "2") (pinfunction "2_2") (pintype "passive"))
      (node (ref "C15") (pin "2") (pinfunction "2_2") (pintype "passive"))
      (node (ref "C16") (pin "1") (pinfunction "1_1") (pintype "passive"))
      (node (ref "C18") (pin "1") (pinfunction "1_1") (pintype "passive"))
      (node (ref "C20") (pin "2") (pinfunction "2_2") (pintype "passive"))
      (node (ref "C21") (pin "2") (pinfunction "2_2") (pintype "passive"))
      (node (ref "C23") (pin "1") (pinfunction "1_1") (pintype "passive"))
      (node (ref "C31") (pin "2") (pinfunction "2_2") (pintype "passive"))
      (node (ref "C33") (pin "2") (pinfunction "2_2") (pintype "passive"))
      (node (ref "C34") (pin "1") (pinfunction "1_1") (pintype "passive"))
      (node (ref "C35") (pin "1") (pinfunction "1_1") (pintype "passive"))
      (node (ref "C36") (pin "2") (pinfunction "2_2") (pintype "passive"))
      (node (ref "C37") (pin "2") (pinfunction "2_2") (pintype "passive"))
      (node (ref "C39") (pin "2") (pinfunction "2_2") (pintype "passive"))
      (node (ref "C4") (pin "2") (pinfunction "2_2") (pintype "passive"))
      (node (ref "C40") (pin "2") (pinfunction "2_2") (pintype "passive"))
      (node (ref "C41") (pin "2") (pinfunction "2_2") (pintype "passive"))
      (node (ref "C42") (pin "2") (pinfunction "2_2") (pintype "passive"))
      (node (ref "C43") (pin "2") (pinfunction "2_2") (pintype "passive"))
      (node (ref "C44") (pin "2") (pinfunction "2_2") (pintype "passive"))
      (node (ref "C5") (pin "-") (pinfunction "-_-") (pintype "passive"))
      (node (ref "C50") (pin "2") (pinfunction "2_2") (pintype "passive"))
      (node (ref "C6") (pin "2") (pinfunction "2_2") (pintype "passive"))
      (node (ref "C7") (pin "2") (pinfunction "2_2") (pintype "passive"))
      (node (ref "C8") (pin "2") (pinfunction "2_2") (pintype "passive"))
      (node (ref "C9") (pin "2") (pinfunction "2_2") (pintype "passive"))
      (node (ref "D1") (pin "A") (pinfunction "A_A") (pintype "passive"))
      (node (ref "D2") (pin "A") (pinfunction "A_A") (pintype "passive"))
      (node (ref "D5") (pin "A") (pinfunction "A_A") (pintype "passive"))
      (node (ref "IC1") (pin "1") (pinfunction "GND_1") (pintype "bidirectional"))
      (node (ref "IC1") (pin "21") (pinfunction "BLANK_21") (pintype "bidirectional"))
      (node (ref "IC11") (pin "1") (pinfunction "C_1") (pintype "passive"))
      (node (ref "IC2") (pin "2") (pinfunction "GND_2") (pintype "passive"))
      (node (ref "IC3") (pin "6") (pinfunction "INH_6") (pintype "input"))
      (node (ref "IC3") (pin "7") (pinfunction "VEE_7") (pintype "power_in"))
      (node (ref "IC3") (pin "8") (pinfunction "GND_8") (pintype "power_in"))
      (node (ref "IC7") (pin "2") (pinfunction "GND_2") (pintype "passive"))
      (node (ref "IC9") (pin "11") (pinfunction "V-_11") (pintype "power_in"))
      (node (ref "IC9") (pin "12") (pinfunction "+IN_12") (pintype "input"))
      (node (ref "J1") (pin "P1") (pinfunction "1_P1") (pintype "passive"))
      (node (ref "J1") (pin "P2") (pinfunction "2_P2") (pintype "passive"))
      (node (ref "J10") (pin "P1") (pinfunction "1_P1") (pintype "passive"))
      (node (ref "J11") (pin "P1") (pinfunction "1_P1") (pintype "passive"))
      (node (ref "J12") (pin "P1") (pinfunction "1_P1") (pintype "passive"))
      (node (ref "J2") (pin "P1") (pinfunction "1_P1") (pintype "passive"))
      (node (ref "J2") (pin "P2") (pinfunction "2_P2") (pintype "passive"))
      (node (ref "J3") (pin "P1") (pinfunction "1_P1") (pintype "passive"))
      (node (ref "J3") (pin "P2") (pinfunction "2_P2") (pintype "passive"))
      (node (ref "J4") (pin "P1") (pinfunction "1_P1") (pintype "passive"))
      (node (ref "J4") (pin "P2") (pinfunction "2_P2") (pintype "passive"))
      (node (ref "J5") (pin "P1") (pinfunction "1_P1") (pintype "passive"))
      (node (ref "J5") (pin "P2") (pinfunction "2_P2") (pintype "passive"))
      (node (ref "J6") (pin "P1") (pinfunction "1_P1") (pintype "passive"))
      (node (ref "J6") (pin "P2") (pinfunction "2_P2") (pintype "passive"))
      (node (ref "J7") (pin "P1") (pinfunction "1_P1") (pintype "passive"))
      (node (ref "J8") (pin "P1") (pinfunction "1_P1") (pintype "passive"))
      (node (ref "J9") (pin "P1") (pinfunction "1_P1") (pintype "passive"))
      (node (ref "JP2") (pin "1") (pinfunction "1_1") (pintype "passive"))
      (node (ref "JP6") (pin "1") (pinfunction "1_1") (pintype "passive"))
      (node (ref "JP8") (pin "3") (pinfunction "3_3") (pintype "passive"))
      (node (ref "JP8") (pin "4") (pinfunction "4_4") (pintype "passive"))
      (node (ref "JP8") (pin "5") (pinfunction "5_5") (pintype "passive"))
      (node (ref "JP8") (pin "6") (pinfunction "6_6") (pintype "passive"))
      (node (ref "JP8") (pin "7") (pinfunction "7_7") (pintype "passive"))
      (node (ref "JP8") (pin "8") (pinfunction "8_8") (pintype "passive"))
      (node (ref "POT_A") (pin "P$3") (pinfunction "A_P$3") (pintype "passive"))
      (node (ref "POT_B") (pin "P$3") (pinfunction "A_P$3") (pintype "passive"))
      (node (ref "POT_C") (pin "P$3") (pinfunction "A_P$3") (pintype "passive"))
      (node (ref "Q2") (pin "2") (pinfunction "LID1_2") (pintype "power_in"))
      (node (ref "Q2") (pin "4") (pinfunction "LID2_4") (pintype "power_in"))
      (node (ref "Q5") (pin "E") (pinfunction "E_E") (pintype "passive"))
      (node (ref "Q6") (pin "E") (pinfunction "E_E") (pintype "passive"))
      (node (ref "Q7") (pin "E") (pinfunction "E_E") (pintype "passive"))
      (node (ref "R13") (pin "2") (pinfunction "2_2") (pintype "passive"))
      (node (ref "R17") (pin "2") (pinfunction "2_2") (pintype "passive"))
      (node (ref "R50") (pin "2") (pinfunction "2_2") (pintype "passive"))
      (node (ref "R69") (pin "1") (pinfunction "1_1") (pintype "passive"))
      (node (ref "R70") (pin "1") (pinfunction "1_1") (pintype "passive"))
      (node (ref "R71") (pin "1") (pinfunction "1_1") (pintype "passive"))
      (node (ref "R9") (pin "2") (pinfunction "2_2") (pintype "passive"))
      (node (ref "SLD_A") (pin "1") (pinfunction "A_1") (pintype "passive"))
      (node (ref "SLD_B") (pin "1") (pinfunction "A_1") (pintype "passive"))
      (node (ref "SLD_C") (pin "1") (pinfunction "A_1") (pintype "passive"))
      (node (ref "SW_A") (pin "1") (pinfunction "1_1") (pintype "passive"))
      (node (ref "SW_A") (pin "2") (pinfunction "2_2") (pintype "passive"))
      (node (ref "SW_B") (pin "1") (pinfunction "1_1") (pintype "passive"))
      (node (ref "SW_B") (pin "2") (pinfunction "2_2") (pintype "passive"))
      (node (ref "SW_C") (pin "1") (pinfunction "1_1") (pintype "passive"))
      (node (ref "SW_C") (pin "2") (pinfunction "2_2") (pintype "passive"))
      (node (ref "U1") (pin "16") (pinfunction "VSS_2_16") (pintype "power_in"))
      (node (ref "U1") (pin "31") (pinfunction "BOOT0_31") (pintype "input"))
      (node (ref "U1") (pin "32") (pinfunction "VSS_1_32") (pintype "power_in"))
      (node (ref "U2") (pin "10") (pinfunction "+IN_10") (pintype "input"))
      (node (ref "U2") (pin "11") (pinfunction "V-_11") (pintype "power_in"))
      (node (ref "U2") (pin "12") (pinfunction "+IN_12") (pintype "input"))
      (node (ref "U2") (pin "3") (pinfunction "+IN_3") (pintype "input"))
      (node (ref "U2") (pin "5") (pinfunction "+IN_5") (pintype "input"))
      (node (ref "U4") (pin "10") (pinfunction "+IN_10") (pintype "input"))
      (node (ref "U4") (pin "12") (pinfunction "+IN_12") (pintype "input"))
      (node (ref "U4") (pin "3") (pinfunction "+IN_3") (pintype "input"))
      (node (ref "U4") (pin "5") (pinfunction "+IN_5") (pintype "input"))
    )
    (net (code "24") (name "LEDS_SCK") (class "Default")
      (node (ref "IC1") (pin "3") (pinfunction "SCLK_3") (pintype "bidirectional"))
      (node (ref "U1") (pin "26") (pinfunction "PB3_26") (pintype "bidirectional"))
    )
    (net (code "25") (name "LEDS_SIN") (class "Default")
      (node (ref "IC1") (pin "2") (pinfunction "SIN_2") (pintype "bidirectional"))
      (node (ref "U1") (pin "28") (pinfunction "PB5_28") (pintype "bidirectional"))
    )
    (net (code "26") (name "N_U") (class "Default")
      (node (ref "U2") (pin "6") (pinfunction "-IN_6") (pintype "input"))
      (node (ref "U2") (pin "7") (pinfunction "OUT_7") (pintype "output"))
    )
    (net (code "27") (name "Net-(C13-Pad1)") (class "Default")
      (node (ref "C13") (pin "1") (pinfunction "1_1") (pintype "passive"))
      (node (ref "D3") (pin "C") (pinfunction "C_C") (pintype "passive"))
      (node (ref "L3") (pin "1") (pinfunction "1_1") (pintype "passive"))
      (node (ref "L4") (pin "2") (pinfunction "2_2") (pintype "passive"))
      (node (ref "L5") (pin "2") (pinfunction "2_2") (pintype "passive"))
    )
    (net (code "28") (name "Net-(C34-Pad2)") (class "Default")
      (node (ref "C34") (pin "2") (pinfunction "2_2") (pintype "passive"))
      (node (ref "Q2") (pin "1") (pinfunction "1_1") (pintype "passive"))
      (node (ref "R22") (pin "2") (pinfunction "2_2") (pintype "passive"))
    )
    (net (code "29") (name "Net-(D1-PadC)") (class "Default")
      (node (ref "D1") (pin "C") (pinfunction "C_C") (pintype "passive"))
      (node (ref "Q7") (pin "B") (pinfunction "B_B") (pintype "passive"))
      (node (ref "R66") (pin "2") (pinfunction "2_2") (pintype "passive"))
      (node (ref "R69") (pin "2") (pinfunction "2_2") (pintype "passive"))
    )
    (net (code "30") (name "Net-(D2-PadC)") (class "Default")
      (node (ref "D2") (pin "C") (pinfunction "C_C") (pintype "passive"))
      (node (ref "Q5") (pin "B") (pinfunction "B_B") (pintype "passive"))
      (node (ref "R67") (pin "2") (pinfunction "2_2") (pintype "passive"))
      (node (ref "R70") (pin "2") (pinfunction "2_2") (pintype "passive"))
    )
    (net (code "31") (name "Net-(D4-PadA)") (class "Default")
      (node (ref "D4") (pin "A") (pinfunction "A_A") (pintype "passive"))
      (node (ref "L1") (pin "2") (pinfunction "2_2") (pintype "passive"))
    )
    (net (code "32") (name "Net-(D5-PadC)") (class "Default")
      (node (ref "D5") (pin "C") (pinfunction "C_C") (pintype "passive"))
      (node (ref "Q6") (pin "B") (pinfunction "B_B") (pintype "passive"))
      (node (ref "R68") (pin "2") (pinfunction "2_2") (pintype "passive"))
      (node (ref "R71") (pin "2") (pinfunction "2_2") (pintype "passive"))
    )
    (net (code "33") (name "Net-(IC1-IREF)") (class "Default")
      (node (ref "IC1") (pin "23") (pinfunction "IREF_23") (pintype "bidirectional"))
      (node (ref "R50") (pin "1") (pinfunction "1_1") (pintype "passive"))
    )
    (net (code "34") (name "Net-(IC1-OUT1)") (class "Default")
      (node (ref "IC1") (pin "6") (pinfunction "OUT1_6") (pintype "bidirectional"))
      (node (ref "R31") (pin "2") (pinfunction "2_2") (pintype "passive"))
    )
    (net (code "35") (name "Net-(IC1-OUT2)") (class "Default")
      (node (ref "IC1") (pin "7") (pinfunction "OUT2_7") (pintype "bidirectional"))
      (node (ref "MODE_C") (pin "RED_C") (pinfunction "RED_RED_C") (pintype "bidirectional"))
    )
    (net (code "36") (name "Net-(IC1-OUT3)") (class "Default")
      (node (ref "IC1") (pin "8") (pinfunction "OUT3_8") (pintype "bidirectional"))
      (node (ref "MODE_C") (pin "GREEN_C") (pinfunction "GRN_GREEN_C") (pintype "bidirectional"))
    )
    (net (code "37") (name "Net-(IC1-OUT4)") (class "Default")
      (node (ref "IC1") (pin "9") (pinfunction "OUT4_9") (pintype "bidirectional"))
      (node (ref "MODE_A") (pin "GREEN_C") (pinfunction "GRN_GREEN_C") (pintype "bidirectional"))
    )
    (net (code "38") (name "Net-(IC1-OUT5)") (class "Default")
      (node (ref "IC1") (pin "10") (pinfunction "OUT5_10") (pintype "bidirectional"))
      (node (ref "MODE_A") (pin "RED_C") (pinfunction "RED_RED_C") (pintype "bidirectional"))
    )
    (net (code "39") (name "Net-(IC1-OUT6)") (class "Default")
      (node (ref "IC1") (pin "11") (pinfunction "OUT6_11") (pintype "bidirectional"))
      (node (ref "MODE_B") (pin "GREEN_C") (pinfunction "GRN_GREEN_C") (pintype "bidirectional"))
    )
    (net (code "40") (name "Net-(IC1-OUT7)") (class "Default")
      (node (ref "IC1") (pin "12") (pinfunction "OUT7_12") (pintype "bidirectional"))
      (node (ref "MODE_B") (pin "RED_C") (pinfunction "RED_RED_C") (pintype "bidirectional"))
    )
    (net (code "41") (name "Net-(IC1-OUT8)") (class "Default")
      (node (ref "IC1") (pin "13") (pinfunction "OUT8_13") (pintype "bidirectional"))
      (node (ref "LED10") (pin "GREEN_C") (pinfunction "GRN_GREEN_C") (pintype "bidirectional"))
    )
    (net (code "42") (name "Net-(IC1-OUT9)") (class "Default")
      (node (ref "IC1") (pin "14") (pinfunction "OUT9_14") (pintype "bidirectional"))
      (node (ref "LED10") (pin "RED_C") (pinfunction "RED_RED_C") (pintype "bidirectional"))
    )
    (net (code "43") (name "Net-(IC1-OUT10)") (class "Default")
      (node (ref "IC1") (pin "15") (pinfunction "OUT10_15") (pintype "bidirectional"))
      (node (ref "LED11") (pin "RED_C") (pinfunction "RED_RED_C") (pintype "bidirectional"))
    )
    (net (code "44") (name "Net-(IC1-OUT11)") (class "Default")
      (node (ref "IC1") (pin "16") (pinfunction "OUT11_16") (pintype "bidirectional"))
      (node (ref "LED11") (pin "GREEN_C") (pinfunction "GRN_GREEN_C") (pintype "bidirectional"))
    )
    (net (code "45") (name "Net-(IC1-OUT12)") (class "Default")
      (node (ref "IC1") (pin "17") (pinfunction "OUT12_17") (pintype "bidirectional"))
      (node (ref "LED12") (pin "RED_C") (pinfunction "RED_RED_C") (pintype "bidirectional"))
    )
    (net (code "46") (name "Net-(IC1-OUT13)") (class "Default")
      (node (ref "IC1") (pin "18") (pinfunction "OUT13_18") (pintype "bidirectional"))
      (node (ref "LED12") (pin "GREEN_C") (pinfunction "GRN_GREEN_C") (pintype "bidirectional"))
    )
    (net (code "47") (name "Net-(IC1-OUT14)") (class "Default")
      (node (ref "IC1") (pin "19") (pinfunction "OUT14_19") (pintype "bidirectional"))
      (node (ref "R19") (pin "2") (pinfunction "2_2") (pintype "passive"))
    )
    (net (code "48") (name "Net-(IC1-OUT15)") (class "Default")
      (node (ref "IC1") (pin "20") (pinfunction "OUT15_20") (pintype "bidirectional"))
      (node (ref "R30") (pin "2") (pinfunction "2_2") (pintype "passive"))
    )
    (net (code "49") (name "Net-(IC1-VCC)") (class "Default")
      (node (ref "C7") (pin "1") (pinfunction "1_1") (pintype "passive"))
      (node (ref "C8") (pin "1") (pinfunction "1_1") (pintype "passive"))
      (node (ref "IC1") (pin "24") (pinfunction "VCC_24") (pintype "bidirectional"))
      (node (ref "L2") (pin "1") (pinfunction "1_1") (pintype "passive"))
    )
    (net (code "50") (name "Net-(IC2-VI)") (class "Default")
      (node (ref "C15") (pin "1") (pinfunction "1_1") (pintype "passive"))
      (node (ref "IC2") (pin "1") (pinfunction "VI_1") (pintype "input"))
      (node (ref "L3") (pin "2") (pinfunction "2_2") (pintype "passive"))
    )
    (net (code "51") (name "Net-(IC3A-X0)") (class "Default")
      (node (ref "IC3") (pin "13") (pinfunction "X0_13") (pintype "bidirectional"))
      (node (ref "POT_C") (pin "P$2") (pinfunction "S_P$2") (pintype "passive"))
    )
    (net (code "52") (name "Net-(IC3A-X1)") (class "Default")
      (node (ref "IC3") (pin "14") (pinfunction "X1_14") (pintype "bidirectional"))
      (node (ref "SLD_C") (pin "2") (pinfunction "S_2") (pintype "passive"))
    )
    (net (code "53") (name "Net-(IC3A-X2)") (class "Default")
      (node (ref "IC3") (pin "15") (pinfunction "X2_15") (pintype "bidirectional"))
      (node (ref "SLD_B") (pin "2") (pinfunction "S_2") (pintype "passive"))
    )
    (net (code "54") (name "Net-(IC3A-X3)") (class "Default")
      (node (ref "IC3") (pin "12") (pinfunction "X3_12") (pintype "bidirectional"))
      (node (ref "POT_A") (pin "P$2") (pinfunction "S_P$2") (pintype "passive"))
    )
    (net (code "55") (name "Net-(IC3A-X4)") (class "Default")
      (node (ref "IC3") (pin "1") (pinfunction "X4_1") (pintype "bidirectional"))
      (node (ref "SLD_A") (pin "2") (pinfunction "S_2") (pintype "passive"))
    )
    (net (code "56") (name "Net-(IC3A-X6)") (class "Default")
      (node (ref "IC3") (pin "2") (pinfunction "X6_2") (pintype "bidirectional"))
      (node (ref "POT_B") (pin "P$2") (pinfunction "S_P$2") (pintype "passive"))
    )
    (net (code "57") (name "Net-(IC7-VI)") (class "Default")
      (node (ref "C20") (pin "1") (pinfunction "1_1") (pintype "passive"))
      (node (ref "IC7") (pin "3") (pinfunction "VI_3") (pintype "input"))
      (node (ref "L4") (pin "1") (pinfunction "1_1") (pintype "passive"))
    )
    (net (code "58") (name "Net-(IC9A-+IN)") (class "Default")
      (node (ref "IC9") (pin "3") (pinfunction "+IN_3") (pintype "input"))
      (node (ref "R8") (pin "2") (pinfunction "2_2") (pintype "passive"))
      (node (ref "R9") (pin "1") (pinfunction "1_1") (pintype "passive"))
    )
    (net (code "59") (name "Net-(IC9A--IN)") (class "Default")
      (node (ref "IC9") (pin "2") (pinfunction "-IN_2") (pintype "input"))
      (node (ref "R10") (pin "1") (pinfunction "1_1") (pintype "passive"))
    )
    (net (code "60") (name "Net-(IC9A-OUT)") (class "Default")
      (node (ref "IC9") (pin "1") (pinfunction "OUT_1") (pintype "output"))
      (node (ref "R7") (pin "2") (pinfunction "2_2") (pintype "passive"))
      (node (ref "R8") (pin "1") (pinfunction "1_1") (pintype "passive"))
    )
    (net (code "61") (name "Net-(IC9B-+IN)") (class "Default")
      (node (ref "IC9") (pin "5") (pinfunction "+IN_5") (pintype "input"))
      (node (ref "R12") (pin "2") (pinfunction "2_2") (pintype "passive"))
      (node (ref "R13") (pin "1") (pinfunction "1_1") (pintype "passive"))
    )
    (net (code "62") (name "Net-(IC9B--IN)") (class "Default")
      (node (ref "IC9") (pin "6") (pinfunction "-IN_6") (pintype "input"))
      (node (ref "R14") (pin "1") (pinfunction "1_1") (pintype "passive"))
    )
    (net (code "63") (name "Net-(IC9B-OUT)") (class "Default")
      (node (ref "IC9") (pin "7") (pinfunction "OUT_7") (pintype "output"))
      (node (ref "R11") (pin "2") (pinfunction "2_2") (pintype "passive"))
      (node (ref "R12") (pin "1") (pinfunction "1_1") (pintype "passive"))
    )
    (net (code "64") (name "Net-(IC9C-+IN)") (class "Default")
      (node (ref "IC9") (pin "10") (pinfunction "+IN_10") (pintype "input"))
      (node (ref "R16") (pin "2") (pinfunction "2_2") (pintype "passive"))
      (node (ref "R17") (pin "1") (pinfunction "1_1") (pintype "passive"))
    )
    (net (code "65") (name "Net-(IC9C--IN)") (class "Default")
      (node (ref "IC9") (pin "9") (pinfunction "-IN_9") (pintype "input"))
      (node (ref "R20") (pin "1") (pinfunction "1_1") (pintype "passive"))
    )
    (net (code "66") (name "Net-(IC9C-OUT)") (class "Default")
      (node (ref "IC9") (pin "8") (pinfunction "OUT_8") (pintype "output"))
      (node (ref "R15") (pin "2") (pinfunction "2_2") (pintype "passive"))
      (node (ref "R16") (pin "1") (pinfunction "1_1") (pintype "passive"))
    )
    (net (code "67") (name "Net-(IC9D--IN)") (class "Default")
      (node (ref "IC9") (pin "13") (pinfunction "-IN_13") (pintype "input"))
      (node (ref "IC9") (pin "14") (pinfunction "OUT_14") (pintype "output"))
    )
    (net (code "68") (name "Net-(J2-3)") (class "Default")
      (node (ref "J2") (pin "P3") (pinfunction "3_P3") (pintype "passive"))
      (node (ref "R4") (pin "2") (pinfunction "2_2") (pintype "passive"))
    )
    (net (code "69") (name "Net-(J5-3)") (class "Default")
      (node (ref "J5") (pin "P3") (pinfunction "3_P3") (pintype "passive"))
      (node (ref "R51") (pin "2") (pinfunction "2_2") (pintype "passive"))
    )
    (net (code "70") (name "Net-(J7-3)") (class "Default")
      (node (ref "J7") (pin "P3") (pinfunction "3_P3") (pintype "passive"))
      (node (ref "R27") (pin "1") (pinfunction "1_1") (pintype "passive"))
      (node (ref "R32") (pin "1") (pinfunction "1_1") (pintype "passive"))
    )
    (net (code "71") (name "Net-(J8-3)") (class "Default")
      (node (ref "J8") (pin "P3") (pinfunction "3_P3") (pintype "passive"))
      (node (ref "R23") (pin "1") (pinfunction "1_1") (pintype "passive"))
      (node (ref "R3") (pin "1") (pinfunction "1_1") (pintype "passive"))
    )
    (net (code "72") (name "Net-(J9-3)") (class "Default")
      (node (ref "J9") (pin "P3") (pinfunction "3_P3") (pintype "passive"))
      (node (ref "R35") (pin "1") (pinfunction "1_1") (pintype "passive"))
      (node (ref "R41") (pin "1") (pinfunction "1_1") (pintype "passive"))
    )
    (net (code "73") (name "Net-(J10-3)") (class "Default")
      (node (ref "J10") (pin "P3") (pinfunction "3_P3") (pintype "passive"))
      (node (ref "R11") (pin "1") (pinfunction "1_1") (pintype "passive"))
    )
    (net (code "74") (name "Net-(J11-3)") (class "Default")
      (node (ref "J11") (pin "P3") (pinfunction "3_P3") (pintype "passive"))
      (node (ref "R15") (pin "1") (pinfunction "1_1") (pintype "passive"))
    )
    (net (code "75") (name "Net-(J12-3)") (class "Default")
      (node (ref "J12") (pin "P3") (pinfunction "3_P3") (pintype "passive"))
      (node (ref "R7") (pin "1") (pinfunction "1_1") (pintype "passive"))
    )
    (net (code "76") (name "Net-(Q2B-2)") (class "Default")
      (node (ref "C35") (pin "2") (pinfunction "2_2") (pintype "passive"))
      (node (ref "Q2") (pin "3") (pinfunction "2_3") (pintype "passive"))
      (node (ref "R21") (pin "2") (pinfunction "2_2") (pintype "passive"))
    )
    (net (code "77") (name "Net-(SLD_AA-C)") (class "Default")
      (node (ref "R19") (pin "1") (pinfunction "1_1") (pintype "passive"))
      (node (ref "SLD_A") (pin "E") (pinfunction "C_E") (pintype "passive"))
    )
    (net (code "78") (name "Net-(SLD_BA-C)") (class "Default")
      (node (ref "R30") (pin "1") (pinfunction "1_1") (pintype "passive"))
      (node (ref "SLD_B") (pin "E") (pinfunction "C_E") (pintype "passive"))
    )
    (net (code "79") (name "Net-(SLD_CA-C)") (class "Default")
      (node (ref "R31") (pin "1") (pinfunction "1_1") (pintype "passive"))
      (node (ref "SLD_C") (pin "E") (pinfunction "C_E") (pintype "passive"))
    )
    (net (code "80") (name "Net-(U1-PF0{slash}OSC_IN)") (class "Default")
      (node (ref "R21") (pin "1") (pinfunction "1_1") (pintype "passive"))
      (node (ref "U1") (pin "2") (pinfunction "PF0/OSC_IN_2") (pintype "bidirectional"))
    )
    (net (code "81") (name "Net-(U1-PF1{slash}OSC_OUT)") (class "Default")
      (node (ref "R22") (pin "1") (pinfunction "1_1") (pintype "passive"))
      (node (ref "U1") (pin "3") (pinfunction "PF1/OSC_OUT_3") (pintype "bidirectional"))
    )
    (net (code "82") (name "Net-(U2A--IN)") (class "Default")
      (node (ref "C12") (pin "1") (pinfunction "1_1") (pintype "passive"))
      (node (ref "R29") (pin "1") (pinfunction "1_1") (pintype "passive"))
      (node (ref "R4") (pin "1") (pinfunction "1_1") (pintype "passive"))
      (node (ref "R5") (pin "2") (pinfunction "2_2") (pintype "passive"))
      (node (ref "U2") (pin "2") (pinfunction "-IN_2") (pintype "input"))
    )
    (net (code "83") (name "Net-(U2C--IN)") (class "Default")
      (node (ref "C26") (pin "1") (pinfunction "1_1") (pintype "passive"))
      (node (ref "R26") (pin "2") (pinfunction "2_2") (pintype "passive"))
      (node (ref "R28") (pin "1") (pinfunction "1_1") (pintype "passive"))
      (node (ref "R6") (pin "1") (pinfunction "1_1") (pintype "passive"))
      (node (ref "U2") (pin "9") (pinfunction "-IN_9") (pintype "input"))
    )
    (net (code "84") (name "Net-(U2D--IN)") (class "Default")
      (node (ref "C28") (pin "1") (pinfunction "1_1") (pintype "passive"))
      (node (ref "R51") (pin "1") (pinfunction "1_1") (pintype "passive"))
      (node (ref "R52") (pin "2") (pinfunction "2_2") (pintype "passive"))
      (node (ref "R53") (pin "1") (pinfunction "1_1") (pintype "passive"))
      (node (ref "U2") (pin "13") (pinfunction "-IN_13") (pintype "input"))
    )
    (net (code "85") (name "Net-(U4A--IN)") (class "Default")
      (node (ref "C1") (pin "1") (pinfunction "1_1") (pintype "passive"))
      (node (ref "R2") (pin "1") (pinfunction "1_1") (pintype "passive"))
      (node (ref "R41") (pin "2") (pinfunction "2_2") (pintype "passive"))
      (node (ref "R47") (pin "1") (pinfunction "1_1") (pintype "passive"))
      (node (ref "U4") (pin "2") (pinfunction "-IN_2") (pintype "input"))
    )
    (net (code "86") (name "Net-(U4A-OUT)") (class "Default")
      (node (ref "C1") (pin "2") (pinfunction "2_2") (pintype "passive"))
      (node (ref "R35") (pin "2") (pinfunction "2_2") (pintype "passive"))
      (node (ref "U4") (pin "1") (pinfunction "OUT_1") (pintype "output"))
    )
    (net (code "87") (name "Net-(U4B--IN)") (class "Default")
      (node (ref "C2") (pin "1") (pinfunction "1_1") (pintype "passive"))
      (node (ref "R23") (pin "2") (pinfunction "2_2") (pintype "passive"))
      (node (ref "R24") (pin "1") (pinfunction "1_1") (pintype "passive"))
      (node (ref "R25") (pin "1") (pinfunction "1_1") (pintype "passive"))
      (node (ref "U4") (pin "6") (pinfunction "-IN_6") (pintype "input"))
    )
    (net (code "88") (name "Net-(U4B-OUT)") (class "Default")
      (node (ref "C2") (pin "2") (pinfunction "2_2") (pintype "passive"))
      (node (ref "R3") (pin "2") (pinfunction "2_2") (pintype "passive"))
      (node (ref "U4") (pin "7") (pinfunction "OUT_7") (pintype "output"))
    )
    (net (code "89") (name "Net-(U4C--IN)") (class "Default")
      (node (ref "C3") (pin "1") (pinfunction "1_1") (pintype "passive"))
      (node (ref "R32") (pin "2") (pinfunction "2_2") (pintype "passive"))
      (node (ref "R33") (pin "1") (pinfunction "1_1") (pintype "passive"))
      (node (ref "R34") (pin "1") (pinfunction "1_1") (pintype "passive"))
      (node (ref "U4") (pin "9") (pinfunction "-IN_9") (pintype "input"))
    )
    (net (code "90") (name "Net-(U4C-OUT)") (class "Default")
      (node (ref "C3") (pin "2") (pinfunction "2_2") (pintype "passive"))
      (node (ref "R27") (pin "2") (pinfunction "2_2") (pintype "passive"))
      (node (ref "U4") (pin "8") (pinfunction "OUT_8") (pintype "output"))
    )
    (net (code "91") (name "Net-(U4D--IN)") (class "Default")
      (node (ref "U4") (pin "13") (pinfunction "-IN_13") (pintype "input"))
      (node (ref "U4") (pin "14") (pinfunction "OUT_14") (pintype "output"))
    )
    (net (code "92") (name "POTS_ADDR_A") (class "Default")
      (node (ref "IC3") (pin "11") (pinfunction "A_11") (pintype "input"))
      (node (ref "U1") (pin "13") (pinfunction "PA7_13") (pintype "bidirectional"))
    )
    (net (code "93") (name "POTS_ADDR_B") (class "Default")
      (node (ref "IC3") (pin "10") (pinfunction "B_10") (pintype "input"))
      (node (ref "U1") (pin "18") (pinfunction "PA8_18") (pintype "bidirectional"))
    )
    (net (code "94") (name "POTS_ADDR_C") (class "Default")
      (node (ref "IC3") (pin "9") (pinfunction "C_9") (pintype "input"))
      (node (ref "U1") (pin "19") (pinfunction "PA9_19") (pintype "bidirectional"))
    )
    (net (code "95") (name "RESET") (class "Default")
      (node (ref "C36") (pin "1") (pinfunction "1_1") (pintype "passive"))
      (node (ref "JP6") (pin "4") (pinfunction "4_4") (pintype "passive"))
      (node (ref "R18") (pin "2") (pinfunction "2_2") (pintype "passive"))
      (node (ref "U1") (pin "4") (pinfunction "NRST_4") (pintype "bidirectional"))
    )
    (net (code "96") (name "SWCLK") (class "Default")
      (node (ref "JP6") (pin "3") (pinfunction "3_3") (pintype "passive"))
      (node (ref "U1") (pin "24") (pinfunction "PA14_24") (pintype "bidirectional"))
    )
    (net (code "97") (name "SWDIO") (class "Default")
      (node (ref "JP6") (pin "2") (pinfunction "2_2") (pintype "passive"))
      (node (ref "U1") (pin "23") (pinfunction "PA13_23") (pintype "bidirectional"))
    )
    (net (code "98") (name "SW_MODE_A") (class "Default")
      (node (ref "SW_A") (pin "3") (pinfunction "3_3") (pintype "passive"))
      (node (ref "SW_A") (pin "4") (pinfunction "4_4") (pintype "passive"))
      (node (ref "U1") (pin "27") (pinfunction "PB4_27") (pintype "bidirectional"))
    )
    (net (code "99") (name "SW_MODE_B") (class "Default")
      (node (ref "SW_B") (pin "3") (pinfunction "3_3") (pintype "passive"))
      (node (ref "SW_B") (pin "4") (pinfunction "4_4") (pintype "passive"))
      (node (ref "U1") (pin "29") (pinfunction "PB6_29") (pintype "bidirectional"))
    )
    (net (code "100") (name "SW_MODE_C") (class "Default")
      (node (ref "SW_C") (pin "3") (pinfunction "3_3") (pintype "passive"))
      (node (ref "SW_C") (pin "4") (pinfunction "4_4") (pintype "passive"))
      (node (ref "U1") (pin "30") (pinfunction "PB7_30") (pintype "bidirectional"))
    )
    (net (code "101") (name "VCC") (class "Default")
      (node (ref "C14") (pin "1") (pinfunction "1_1") (pintype "passive"))
      (node (ref "C21") (pin "1") (pinfunction "1_1") (pintype "passive"))
      (node (ref "C4") (pin "1") (pinfunction "1_1") (pintype "passive"))
      (node (ref "C50") (pin "1") (pinfunction "1_1") (pintype "passive"))
      (node (ref "IC9") (pin "4") (pinfunction "V+_4") (pintype "power_in"))
      (node (ref "JP2") (pin "6") (pinfunction "6_6") (pintype "passive"))
      (node (ref "L5") (pin "1") (pinfunction "1_1") (pintype "passive"))
      (node (ref "U4") (pin "4") (pinfunction "V+_4") (pintype "power_in"))
    )
    (net (code "102") (name "VEE") (class "Default")
      (node (ref "C16") (pin "2") (pinfunction "2_2") (pintype "passive"))
      (node (ref "C18") (pin "2") (pinfunction "2_2") (pintype "passive"))
      (node (ref "C23") (pin "2") (pinfunction "2_2") (pintype "passive"))
      (node (ref "JP2") (pin "5") (pinfunction "5_5") (pintype "passive"))
      (node (ref "L1") (pin "1") (pinfunction "1_1") (pintype "passive"))
      (node (ref "R1") (pin "1") (pinfunction "1_1") (pintype "passive"))
      (node (ref "U4") (pin "11") (pinfunction "V-_11") (pintype "power_in"))
    )
    (net (code "103") (name "unconnected-(IC1-LAT-Pad4)") (class "Default")
      (node (ref "IC1") (pin "4") (pinfunction "LAT_4") (pintype "bidirectional"))
    )
    (net (code "104") (name "unconnected-(IC1-OUT0-Pad5)") (class "Default")
      (node (ref "IC1") (pin "5") (pinfunction "OUT0_5") (pintype "bidirectional"))
    )
    (net (code "105") (name "unconnected-(IC1-SOUT-Pad22)") (class "Default")
      (node (ref "IC1") (pin "22") (pinfunction "SOUT_22") (pintype "bidirectional"))
    )
    (net (code "106") (name "unconnected-(IC3A-X5-Pad5)") (class "Default")
      (node (ref "IC3") (pin "5") (pinfunction "X5_5") (pintype "bidirectional"))
    )
    (net (code "107") (name "unconnected-(IC3A-X7-Pad4)") (class "Default")
      (node (ref "IC3") (pin "4") (pinfunction "X7_4") (pintype "bidirectional"))
    )
    (net (code "108") (name "unconnected-(J7-2-PadP2)") (class "Default")
      (node (ref "J7") (pin "P2") (pinfunction "2_P2") (pintype "passive"))
    )
    (net (code "109") (name "unconnected-(J8-2-PadP2)") (class "Default")
      (node (ref "J8") (pin "P2") (pinfunction "2_P2") (pintype "passive"))
    )
    (net (code "110") (name "unconnected-(J9-2-PadP2)") (class "Default")
      (node (ref "J9") (pin "P2") (pinfunction "2_P2") (pintype "passive"))
    )
    (net (code "111") (name "unconnected-(J10-2-PadP2)") (class "Default")
      (node (ref "J10") (pin "P2") (pinfunction "2_P2") (pintype "passive"))
    )
    (net (code "112") (name "unconnected-(J11-2-PadP2)") (class "Default")
      (node (ref "J11") (pin "P2") (pinfunction "2_P2") (pintype "passive"))
    )
    (net (code "113") (name "unconnected-(J12-2-PadP2)") (class "Default")
      (node (ref "J12") (pin "P2") (pinfunction "2_P2") (pintype "passive"))
    )
  )
)
